# EDUPIC.net
KiCad netlist of a schematic drawn in EAGLE
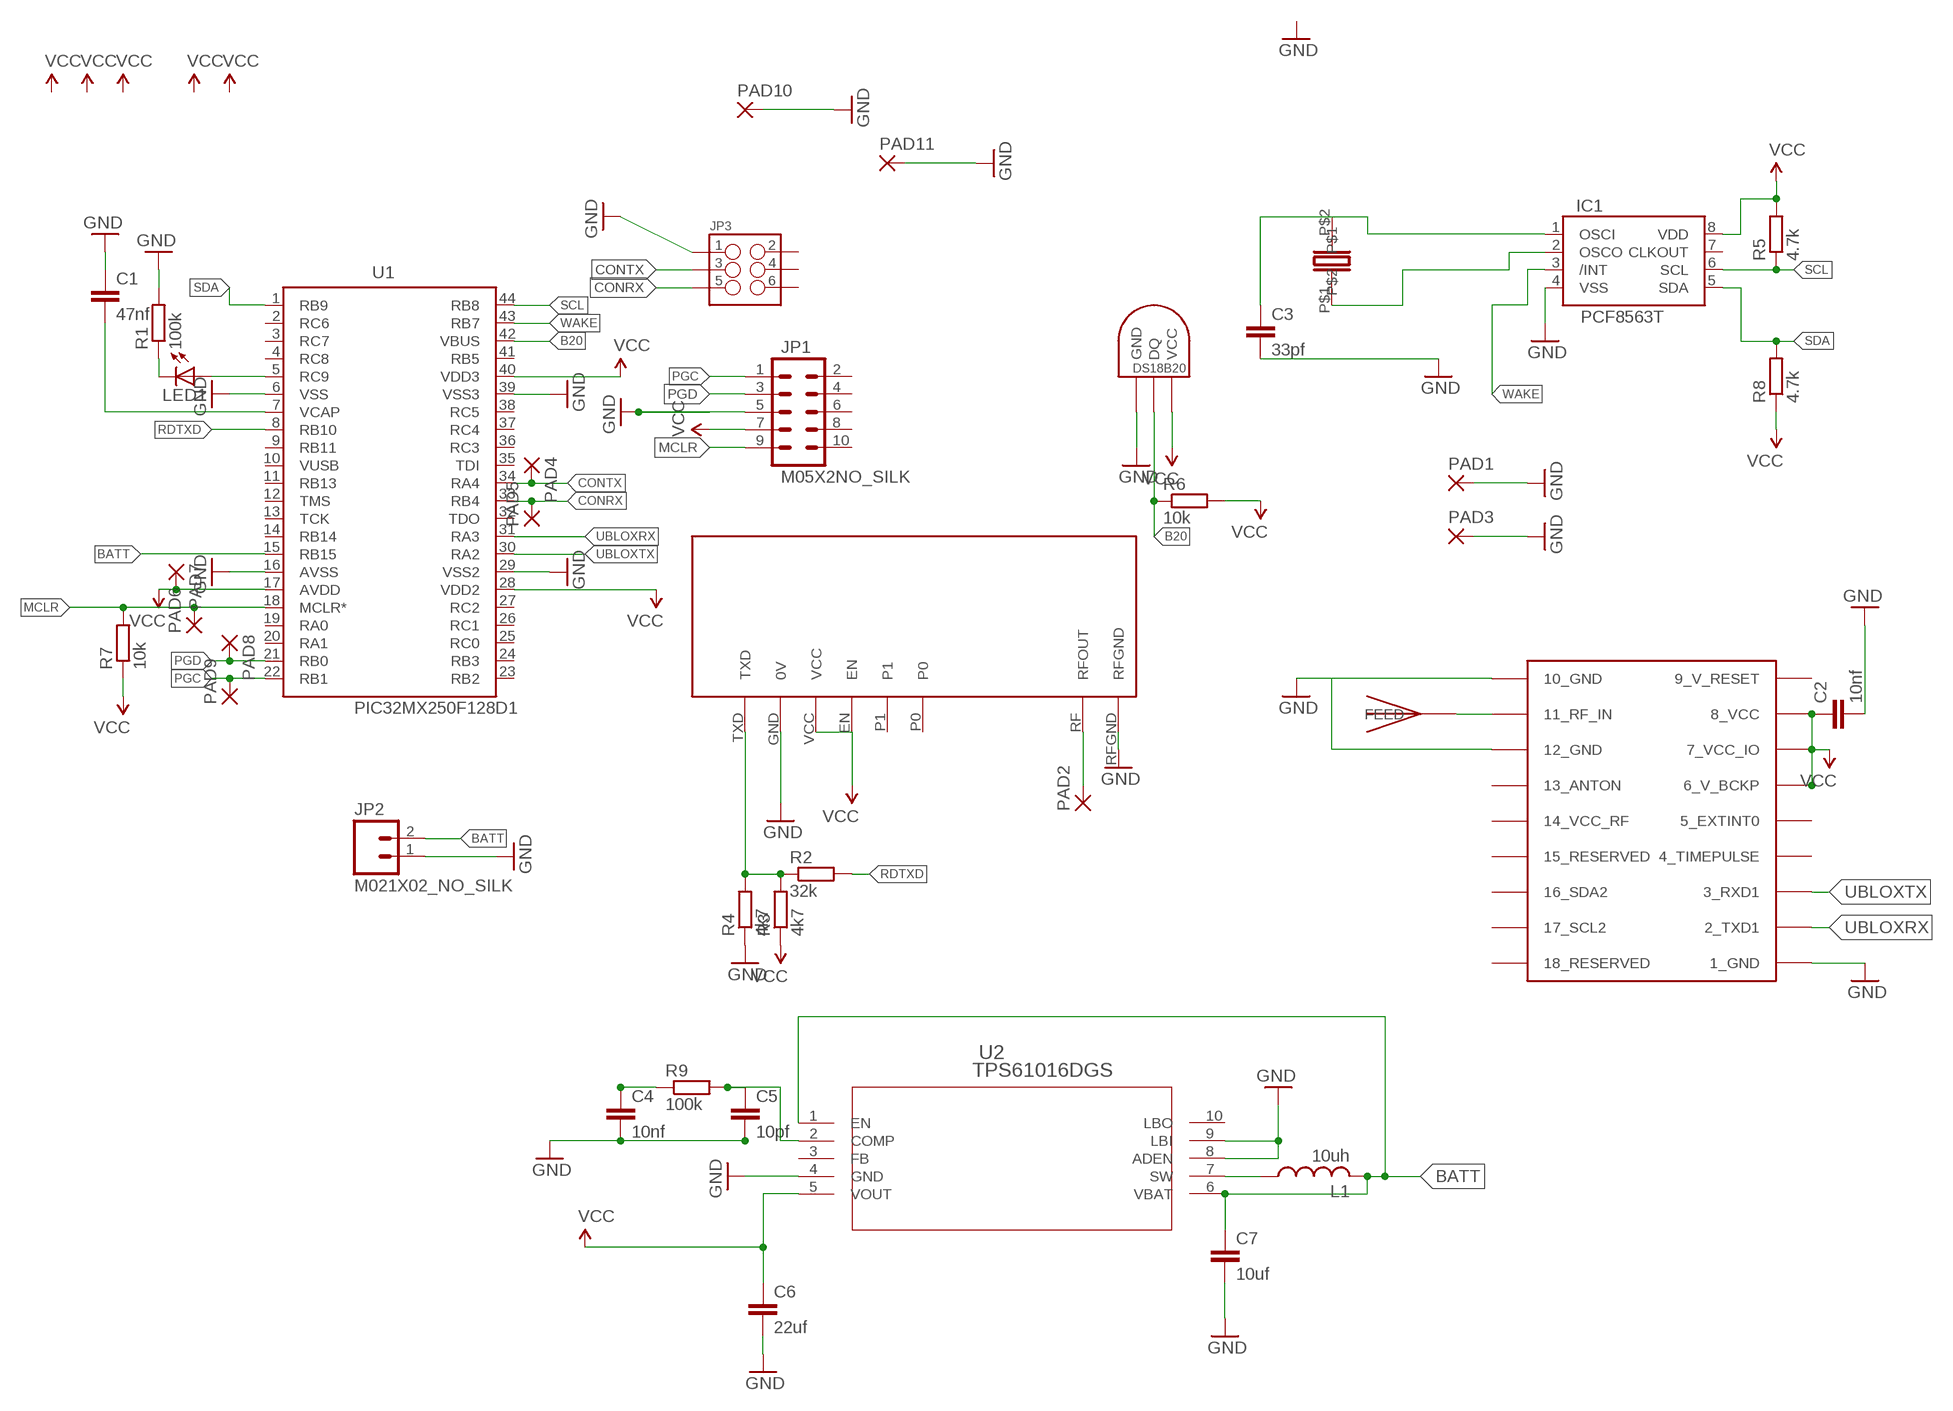
[diagram p0: schematic, sheet 1]

(export (version "E")
  (design (tool "Eeschema 10.0.6"))
  (components
    (comp (ref "C1")
      (value "47nf")
      (footprint "eagle-import:C1206")
      (libsource (lib "eagle-import") (part "C-EUC1206"))
    )
    (comp (ref "C2")
      (value "10nf")
      (footprint "eagle-import:C1206")
      (libsource (lib "eagle-import") (part "C-EUC1206"))
    )
    (comp (ref "C3")
      (value "33pf")
      (footprint "eagle-import:C0805")
      (libsource (lib "eagle-import") (part "C-EUC0805"))
    )
    (comp (ref "C4")
      (value "10nf")
      (footprint "eagle-import:C0805")
      (libsource (lib "eagle-import") (part "C-EUC0805"))
    )
    (comp (ref "C5")
      (value "10pf")
      (footprint "eagle-import:C0805")
      (libsource (lib "eagle-import") (part "C-EUC0805"))
    )
    (comp (ref "C6")
      (value "22uf")
      (footprint "eagle-import:C1812")
      (libsource (lib "eagle-import") (part "C-EUC1812"))
    )
    (comp (ref "C7")
      (value "10uf")
      (footprint "eagle-import:C1206")
      (libsource (lib "eagle-import") (part "C-EUC1206"))
    )
    (comp (ref "IC1")
      (value "PCF8563T")
      (footprint "eagle-import:SO8")
      (libsource (lib "eagle-import") (part "PCF8563T"))
    )
    (comp (ref "JP1")
      (value "M05X2NO_SILK")
      (footprint "eagle-import:2X5_NOSILK")
      (libsource (lib "eagle-import") (part "M05X2NO_SILK"))
    )
    (comp (ref "JP2")
      (value "M021X02_NO_SILK")
      (footprint "eagle-import:1X02_NO_SILK")
      (libsource (lib "eagle-import") (part "M021X02_NO_SILK"))
    )
    (comp (ref "JP3")
      (value "M03X2NO_SILK")
      (footprint "eagle-import:2X3-NS")
      (libsource (lib "eagle-import") (part "M03X2NO_SILK"))
    )
    (comp (ref "L1")
      (value "10uh")
      (footprint "eagle-import:PIS2816")
      (libsource (lib "eagle-import") (part "L-USPIS2816"))
    )
    (comp (ref "LED1")
      (value "LEDCHIP-LED0805")
      (footprint "eagle-import:CHIP-LED0805")
      (libsource (lib "eagle-import") (part "LEDCHIP-LED0805"))
    )
    (comp (ref "PAD1")
      (value "SMD5")
      (footprint "eagle-import:SMD2,54-5,08")
      (libsource (lib "eagle-import") (part "SMD5"))
    )
    (comp (ref "PAD2")
      (value "SMD5")
      (footprint "eagle-import:SMD2,54-5,08")
      (libsource (lib "eagle-import") (part "SMD5"))
    )
    (comp (ref "PAD3")
      (value "SMD5")
      (footprint "eagle-import:SMD2,54-5,08")
      (libsource (lib "eagle-import") (part "SMD5"))
    )
    (comp (ref "PAD4")
      (value "SMD2")
      (footprint "eagle-import:SMD1,27-2,54")
      (libsource (lib "eagle-import") (part "SMD2"))
    )
    (comp (ref "PAD5")
      (value "SMD2")
      (footprint "eagle-import:SMD1,27-2,54")
      (libsource (lib "eagle-import") (part "SMD2"))
    )
    (comp (ref "PAD6")
      (value "SMD2")
      (footprint "eagle-import:SMD1,27-2,54")
      (libsource (lib "eagle-import") (part "SMD2"))
    )
    (comp (ref "PAD7")
      (value "SMD2")
      (footprint "eagle-import:SMD1,27-2,54")
      (libsource (lib "eagle-import") (part "SMD2"))
    )
    (comp (ref "PAD8")
      (value "SMD2")
      (footprint "eagle-import:SMD1,27-2,54")
      (libsource (lib "eagle-import") (part "SMD2"))
    )
    (comp (ref "PAD9")
      (value "SMD2")
      (footprint "eagle-import:SMD1,27-2,54")
      (libsource (lib "eagle-import") (part "SMD2"))
    )
    (comp (ref "PAD10")
      (value "SMD2")
      (footprint "eagle-import:SMD1,27-2,54")
      (libsource (lib "eagle-import") (part "SMD2"))
    )
    (comp (ref "PAD11")
      (value "SMD2")
      (footprint "eagle-import:SMD1,27-2,54")
      (libsource (lib "eagle-import") (part "SMD2"))
    )
    (comp (ref "R1")
      (value "100k")
      (footprint "eagle-import:R0603")
      (libsource (lib "eagle-import") (part "R-EU_R0603"))
    )
    (comp (ref "R2")
      (value "32k")
      (footprint "eagle-import:R1206")
      (libsource (lib "eagle-import") (part "R-EU_R1206"))
    )
    (comp (ref "R3")
      (value "4k7")
      (footprint "eagle-import:R0805")
      (libsource (lib "eagle-import") (part "R-EU_R0805"))
    )
    (comp (ref "R4")
      (value "4k7")
      (footprint "eagle-import:R0805")
      (libsource (lib "eagle-import") (part "R-EU_R0805"))
    )
    (comp (ref "R5")
      (value "4.7k")
      (footprint "eagle-import:R0603")
      (libsource (lib "eagle-import") (part "R-EU_R0603"))
    )
    (comp (ref "R6")
      (value "10k")
      (footprint "eagle-import:R0603")
      (libsource (lib "eagle-import") (part "R-EU_R0603"))
    )
    (comp (ref "R7")
      (value "10k")
      (footprint "eagle-import:R0603")
      (libsource (lib "eagle-import") (part "R-EU_R0603"))
    )
    (comp (ref "R8")
      (value "4.7k")
      (footprint "eagle-import:R0603")
      (libsource (lib "eagle-import") (part "R-EU_R0603"))
    )
    (comp (ref "R9")
      (value "100k")
      (footprint "eagle-import:R0805")
      (libsource (lib "eagle-import") (part "R-EU_R0805"))
    )
    (comp (ref "U$1")
      (value "RADIOMETRIX-MTX2")
      (footprint "eagle-import:RADIOMETRIX-MTX2")
      (libsource (lib "eagle-import") (part "RADIOMETRIX-MTX2"))
    )
    (comp (ref "U$2")
      (value "DS1820SOIC")
      (footprint "eagle-import:DS18B20_SOIC")
      (libsource (lib "eagle-import") (part "DS1820SOIC"))
    )
    (comp (ref "U$3")
      (value "UBLOX_MAX")
      (footprint "eagle-import:UBLOX_MAX")
      (libsource (lib "eagle-import") (part "UBLOX_MAX"))
    )
    (comp (ref "U$4")
      (value "JTI_ANTENNA-1575AT43A40")
      (footprint "eagle-import:JTI_ANTENNA-1575AT43A40")
      (libsource (lib "eagle-import") (part "JTI_ANTENNA-1575AT43A40"))
    )
    (comp (ref "U1")
      (value "PIC32MX250F128D1")
      (footprint "eagle-import:QFP80P1200X1200X120-44N")
      (libsource (lib "eagle-import") (part "PIC32MX250F128D1"))
    )
    (comp (ref "U2")
      (value "TPS61016DGS")
      (footprint "eagle-import:DGS10")
      (fields (field (name "RSPARTNUMBER") "5171220"))
      (libsource (lib "eagle-import") (part "TPS61016DGS"))
    )
    (comp (ref "XTAL")
      (value "3.2X1.5")
      (footprint "eagle-import:3.2X1.5")
      (libsource (lib "eagle-import") (part "3.2X1.5"))
    )
  )
  (nets
    (net (code "1") (name "/9_V_RESET") (class "Default")
      (node (ref "U$3") (pin "9_V_RESET") (pinfunction "9_V_RESET_9_V_RESET") (pintype "power_in"))
    )
    (net (code "2") (name "B20") (class "Default")
      (node (ref "R6") (pin "1") (pinfunction "1_1") (pintype "passive"))
      (node (ref "U$2") (pin "DQ") (pinfunction "DQ_DQ") (pintype "bidirectional"))
      (node (ref "U1") (pin "42") (pinfunction "VBUS_42") (pintype "passive"))
    )
    (net (code "3") (name "BATT") (class "Default")
      (node (ref "C7") (pin "1") (pinfunction "1_1") (pintype "passive"))
      (node (ref "JP2") (pin "2") (pinfunction "2_2") (pintype "passive"))
      (node (ref "L1") (pin "2") (pinfunction "2_2") (pintype "passive"))
      (node (ref "U1") (pin "15") (pinfunction "RB15_15") (pintype "bidirectional"))
      (node (ref "U2") (pin "1") (pinfunction "EN_1") (pintype "input"))
      (node (ref "U2") (pin "6") (pinfunction "VBAT_6") (pintype "power_in"))
    )
    (net (code "4") (name "CONRX") (class "Default")
      (node (ref "JP3") (pin "5") (pinfunction "5_5") (pintype "bidirectional"))
      (node (ref "PAD5") (pin "1") (pinfunction "P_1") (pintype "passive"))
      (node (ref "U1") (pin "33") (pinfunction "RB4_33") (pintype "bidirectional"))
    )
    (net (code "5") (name "CONTX") (class "Default")
      (node (ref "JP3") (pin "3") (pinfunction "3_3") (pintype "bidirectional"))
      (node (ref "PAD4") (pin "1") (pinfunction "P_1") (pintype "passive"))
      (node (ref "U1") (pin "34") (pinfunction "RA4_34") (pintype "bidirectional"))
    )
    (net (code "6") (name "GND") (class "Default")
      (node (ref "C1") (pin "1") (pinfunction "1_1") (pintype "passive"))
      (node (ref "C2") (pin "2") (pinfunction "2_2") (pintype "passive"))
      (node (ref "C3") (pin "2") (pinfunction "2_2") (pintype "passive"))
      (node (ref "C4") (pin "2") (pinfunction "2_2") (pintype "passive"))
      (node (ref "C5") (pin "2") (pinfunction "2_2") (pintype "passive"))
      (node (ref "C6") (pin "2") (pinfunction "2_2") (pintype "passive"))
      (node (ref "C7") (pin "2") (pinfunction "2_2") (pintype "passive"))
      (node (ref "IC1") (pin "4") (pinfunction "VSS_4") (pintype "bidirectional"))
      (node (ref "JP1") (pin "5") (pinfunction "5_5") (pintype "passive"))
      (node (ref "JP2") (pin "1") (pinfunction "1_1") (pintype "passive"))
      (node (ref "JP3") (pin "1") (pinfunction "1_1") (pintype "bidirectional"))
      (node (ref "PAD1") (pin "1") (pinfunction "P_1") (pintype "passive"))
      (node (ref "PAD10") (pin "1") (pinfunction "P_1") (pintype "passive"))
      (node (ref "PAD11") (pin "1") (pinfunction "P_1") (pintype "passive"))
      (node (ref "PAD3") (pin "1") (pinfunction "P_1") (pintype "passive"))
      (node (ref "R1") (pin "2") (pinfunction "2_2") (pintype "passive"))
      (node (ref "R4") (pin "1") (pinfunction "1_1") (pintype "passive"))
      (node (ref "U$1") (pin "GND") (pinfunction "0V_GND") (pintype "bidirectional"))
      (node (ref "U$1") (pin "RFGND") (pinfunction "RFGND_RFGND") (pintype "bidirectional"))
      (node (ref "U$2") (pin "GND") (pinfunction "GND_GND") (pintype "power_in"))
      (node (ref "U$3") (pin "10_GND") (pinfunction "10_GND_10_GND") (pintype "power_in"))
      (node (ref "U$3") (pin "12_GND") (pinfunction "12_GND_12_GND") (pintype "power_in"))
      (node (ref "U$3") (pin "1_GND") (pinfunction "1_GND_1_GND") (pintype "power_in"))
      (node (ref "U1") (pin "16") (pinfunction "AVSS_16") (pintype "power_in"))
      (node (ref "U1") (pin "29") (pinfunction "VSS2_29") (pintype "power_in"))
      (node (ref "U1") (pin "39") (pinfunction "VSS3_39") (pintype "power_in"))
      (node (ref "U1") (pin "6") (pinfunction "VSS_6") (pintype "power_in"))
      (node (ref "U2") (pin "4") (pinfunction "GND_4") (pintype "power_in"))
      (node (ref "U2") (pin "8") (pinfunction "ADEN_8") (pintype "input"))
      (node (ref "U2") (pin "9") (pinfunction "LBI_9") (pintype "input"))
    )
    (net (code "7") (name "MCLR") (class "Default")
      (node (ref "JP1") (pin "9") (pinfunction "9_9") (pintype "passive"))
      (node (ref "PAD6") (pin "1") (pinfunction "P_1") (pintype "passive"))
      (node (ref "R7") (pin "2") (pinfunction "2_2") (pintype "passive"))
      (node (ref "U1") (pin "18") (pinfunction "MCLR*_18") (pintype "input"))
    )
    (net (code "8") (name "Net-(C4-Pad1)") (class "Default")
      (node (ref "C4") (pin "1") (pinfunction "1_1") (pintype "passive"))
      (node (ref "R9") (pin "1") (pinfunction "1_1") (pintype "passive"))
    )
    (net (code "9") (name "Net-(IC1-OSCI)") (class "Default")
      (node (ref "C3") (pin "1") (pinfunction "1_1") (pintype "passive"))
      (node (ref "IC1") (pin "1") (pinfunction "OSCI_1") (pintype "bidirectional"))
      (node (ref "XTAL") (pin "P$2") (pinfunction "P$2_P$2") (pintype "bidirectional"))
    )
    (net (code "10") (name "Net-(IC1-OSCO)") (class "Default")
      (node (ref "IC1") (pin "2") (pinfunction "OSCO_2") (pintype "bidirectional"))
      (node (ref "XTAL") (pin "P$1") (pinfunction "P$1_P$1") (pintype "bidirectional"))
    )
    (net (code "11") (name "Net-(LED1-PadC)") (class "Default")
      (node (ref "LED1") (pin "C") (pinfunction "C_C") (pintype "passive"))
      (node (ref "R1") (pin "1") (pinfunction "1_1") (pintype "passive"))
    )
    (net (code "12") (name "Net-(PAD2-P)") (class "Default")
      (node (ref "PAD2") (pin "1") (pinfunction "P_1") (pintype "passive"))
      (node (ref "U$1") (pin "RF") (pinfunction "RFOUT_RF") (pintype "bidirectional"))
    )
    (net (code "13") (name "Net-(R2-Pad1)") (class "Default")
      (node (ref "R2") (pin "1") (pinfunction "1_1") (pintype "passive"))
      (node (ref "R3") (pin "2") (pinfunction "2_2") (pintype "passive"))
      (node (ref "R4") (pin "2") (pinfunction "2_2") (pintype "passive"))
      (node (ref "U$1") (pin "TXD") (pinfunction "TXD_TXD") (pintype "bidirectional"))
    )
    (net (code "14") (name "Net-(U$3-Pad11_RF_IN)") (class "Default")
      (node (ref "U$3") (pin "11_RF_IN") (pinfunction "11_RF_IN_11_RF_IN") (pintype "bidirectional"))
      (node (ref "U$4") (pin "FEED") (pinfunction "FEED_FEED") (pintype "bidirectional"))
    )
    (net (code "15") (name "Net-(U1-RC9)") (class "Default")
      (node (ref "LED1") (pin "A") (pinfunction "A_A") (pintype "passive"))
      (node (ref "U1") (pin "5") (pinfunction "RC9_5") (pintype "bidirectional"))
    )
    (net (code "16") (name "Net-(U1-VCAP)") (class "Default")
      (node (ref "C1") (pin "2") (pinfunction "2_2") (pintype "passive"))
      (node (ref "U1") (pin "7") (pinfunction "VCAP_7") (pintype "bidirectional"))
    )
    (net (code "17") (name "Net-(U2-COMP)") (class "Default")
      (node (ref "C5") (pin "1") (pinfunction "1_1") (pintype "passive"))
      (node (ref "R9") (pin "2") (pinfunction "2_2") (pintype "passive"))
      (node (ref "U2") (pin "2") (pinfunction "COMP_2") (pintype "input"))
    )
    (net (code "18") (name "Net-(U2-SW)") (class "Default")
      (node (ref "L1") (pin "1") (pinfunction "1_1") (pintype "passive"))
      (node (ref "U2") (pin "7") (pinfunction "SW_7") (pintype "input"))
    )
    (net (code "19") (name "PGC") (class "Default")
      (node (ref "JP1") (pin "1") (pinfunction "1_1") (pintype "passive"))
      (node (ref "PAD9") (pin "1") (pinfunction "P_1") (pintype "passive"))
      (node (ref "U1") (pin "22") (pinfunction "RB1_22") (pintype "bidirectional"))
    )
    (net (code "20") (name "PGD") (class "Default")
      (node (ref "JP1") (pin "3") (pinfunction "3_3") (pintype "passive"))
      (node (ref "PAD8") (pin "1") (pinfunction "P_1") (pintype "passive"))
      (node (ref "U1") (pin "21") (pinfunction "RB0_21") (pintype "bidirectional"))
    )
    (net (code "21") (name "RDTXD") (class "Default")
      (node (ref "R2") (pin "2") (pinfunction "2_2") (pintype "passive"))
      (node (ref "U1") (pin "8") (pinfunction "RB10_8") (pintype "bidirectional"))
    )
    (net (code "22") (name "SCL") (class "Default")
      (node (ref "IC1") (pin "6") (pinfunction "SCL_6") (pintype "bidirectional"))
      (node (ref "R5") (pin "1") (pinfunction "1_1") (pintype "passive"))
      (node (ref "U1") (pin "44") (pinfunction "RB8_44") (pintype "bidirectional"))
    )
    (net (code "23") (name "SDA") (class "Default")
      (node (ref "IC1") (pin "5") (pinfunction "SDA_5") (pintype "bidirectional"))
      (node (ref "R8") (pin "2") (pinfunction "2_2") (pintype "passive"))
      (node (ref "U1") (pin "1") (pinfunction "RB9_1") (pintype "bidirectional"))
    )
    (net (code "24") (name "UBLOXRX") (class "Default")
      (node (ref "U$3") (pin "2_TXD1") (pinfunction "2_TXD1_2_TXD1") (pintype "bidirectional"))
      (node (ref "U1") (pin "31") (pinfunction "RA3_31") (pintype "bidirectional"))
    )
    (net (code "25") (name "UBLOXTX") (class "Default")
      (node (ref "U$3") (pin "3_RXD1") (pinfunction "3_RXD1_3_RXD1") (pintype "bidirectional"))
      (node (ref "U1") (pin "30") (pinfunction "RA2_30") (pintype "bidirectional"))
    )
    (net (code "26") (name "VCC") (class "Default")
      (node (ref "C2") (pin "1") (pinfunction "1_1") (pintype "passive"))
      (node (ref "C6") (pin "1") (pinfunction "1_1") (pintype "passive"))
      (node (ref "IC1") (pin "8") (pinfunction "VDD_8") (pintype "bidirectional"))
      (node (ref "JP1") (pin "7") (pinfunction "7_7") (pintype "passive"))
      (node (ref "PAD7") (pin "1") (pinfunction "P_1") (pintype "passive"))
      (node (ref "R3") (pin "1") (pinfunction "1_1") (pintype "passive"))
      (node (ref "R5") (pin "2") (pinfunction "2_2") (pintype "passive"))
      (node (ref "R6") (pin "2") (pinfunction "2_2") (pintype "passive"))
      (node (ref "R7") (pin "1") (pinfunction "1_1") (pintype "passive"))
      (node (ref "R8") (pin "1") (pinfunction "1_1") (pintype "passive"))
      (node (ref "U$1") (pin "EN") (pinfunction "EN_EN") (pintype "bidirectional"))
      (node (ref "U$1") (pin "VCC") (pinfunction "VCC_VCC") (pintype "bidirectional"))
      (node (ref "U$2") (pin "VCC") (pinfunction "VCC_VCC") (pintype "power_in"))
      (node (ref "U$3") (pin "6_V_BCKP") (pinfunction "6_V_BCKP_6_V_BCKP") (pintype "bidirectional"))
      (node (ref "U$3") (pin "7_VCC_IO") (pinfunction "7_VCC_IO_7_VCC_IO") (pintype "power_in"))
      (node (ref "U$3") (pin "8_VCC") (pinfunction "8_VCC_8_VCC") (pintype "power_in"))
      (node (ref "U1") (pin "17") (pinfunction "AVDD_17") (pintype "power_in"))
      (node (ref "U1") (pin "28") (pinfunction "VDD2_28") (pintype "power_in"))
      (node (ref "U1") (pin "40") (pinfunction "VDD3_40") (pintype "power_in"))
      (node (ref "U2") (pin "5") (pinfunction "VOUT_5") (pintype "output"))
    )
    (net (code "27") (name "WAKE") (class "Default")
      (node (ref "IC1") (pin "3") (pinfunction "/INT_3") (pintype "bidirectional"))
      (node (ref "U1") (pin "43") (pinfunction "RB7_43") (pintype "bidirectional"))
    )
    (net (code "28") (name "unconnected-(IC1-CLKOUT-Pad7)") (class "Default")
      (node (ref "IC1") (pin "7") (pinfunction "CLKOUT_7") (pintype "bidirectional"))
    )
    (net (code "29") (name "unconnected-(JP1-Pad2)") (class "Default")
      (node (ref "JP1") (pin "2") (pinfunction "2_2") (pintype "passive"))
    )
    (net (code "30") (name "unconnected-(JP1-Pad4)") (class "Default")
      (node (ref "JP1") (pin "4") (pinfunction "4_4") (pintype "passive"))
    )
    (net (code "31") (name "unconnected-(JP1-Pad6)") (class "Default")
      (node (ref "JP1") (pin "6") (pinfunction "6_6") (pintype "passive"))
    )
    (net (code "32") (name "unconnected-(JP1-Pad8)") (class "Default")
      (node (ref "JP1") (pin "8") (pinfunction "8_8") (pintype "passive"))
    )
    (net (code "33") (name "unconnected-(JP1-Pad10)") (class "Default")
      (node (ref "JP1") (pin "10") (pinfunction "10_10") (pintype "passive"))
    )
    (net (code "34") (name "unconnected-(JP3-Pad2)") (class "Default")
      (node (ref "JP3") (pin "2") (pinfunction "2_2") (pintype "bidirectional"))
    )
    (net (code "35") (name "unconnected-(JP3-Pad4)") (class "Default")
      (node (ref "JP3") (pin "4") (pinfunction "4_4") (pintype "bidirectional"))
    )
    (net (code "36") (name "unconnected-(JP3-Pad6)") (class "Default")
      (node (ref "JP3") (pin "6") (pinfunction "6_6") (pintype "bidirectional"))
    )
    (net (code "37") (name "unconnected-(U$1-PadP0)") (class "Default")
      (node (ref "U$1") (pin "P0") (pinfunction "P0_P0") (pintype "bidirectional"))
    )
    (net (code "38") (name "unconnected-(U$1-PadP1)") (class "Default")
      (node (ref "U$1") (pin "P1") (pinfunction "P1_P1") (pintype "bidirectional"))
    )
    (net (code "39") (name "unconnected-(U$3-Pad4_TIMEPULSE)") (class "Default")
      (node (ref "U$3") (pin "4_TIMEPULSE") (pinfunction "4_TIMEPULSE_4_TIMEPULSE") (pintype "bidirectional"))
    )
    (net (code "40") (name "unconnected-(U$3-Pad5_EXTINT0)") (class "Default")
      (node (ref "U$3") (pin "5_EXTINT0") (pinfunction "5_EXTINT0_5_EXTINT0") (pintype "bidirectional"))
    )
    (net (code "41") (name "unconnected-(U$3-Pad13_ANTON)") (class "Default")
      (node (ref "U$3") (pin "13_ANTON") (pinfunction "13_ANTON_13_ANTON") (pintype "bidirectional"))
    )
    (net (code "42") (name "unconnected-(U$3-Pad14_VCC_RF)") (class "Default")
      (node (ref "U$3") (pin "14_VCC_RF") (pinfunction "14_VCC_RF_14_VCC_RF") (pintype "bidirectional"))
    )
    (net (code "43") (name "unconnected-(U$3-Pad15_RESERVED)") (class "Default")
      (node (ref "U$3") (pin "15_RESERVED") (pinfunction "15_RESERVED_15_RESERVED") (pintype "bidirectional"))
    )
    (net (code "44") (name "unconnected-(U$3-Pad16_SDA2)") (class "Default")
      (node (ref "U$3") (pin "16_SDA2") (pinfunction "16_SDA2_16_SDA2") (pintype "bidirectional"))
    )
    (net (code "45") (name "unconnected-(U$3-Pad17_SCL2)") (class "Default")
      (node (ref "U$3") (pin "17_SCL2") (pinfunction "17_SCL2_17_SCL2") (pintype "bidirectional"))
    )
    (net (code "46") (name "unconnected-(U$3-Pad18_RESERVED)") (class "Default")
      (node (ref "U$3") (pin "18_RESERVED") (pinfunction "18_RESERVED_18_RESERVED") (pintype "bidirectional"))
    )
    (net (code "47") (name "unconnected-(U1-RA0-Pad19)") (class "Default")
      (node (ref "U1") (pin "19") (pinfunction "RA0_19") (pintype "bidirectional"))
    )
    (net (code "48") (name "unconnected-(U1-RA1-Pad20)") (class "Default")
      (node (ref "U1") (pin "20") (pinfunction "RA1_20") (pintype "bidirectional"))
    )
    (net (code "49") (name "unconnected-(U1-RB2-Pad23)") (class "Default")
      (node (ref "U1") (pin "23") (pinfunction "RB2_23") (pintype "bidirectional"))
    )
    (net (code "50") (name "unconnected-(U1-RB3-Pad24)") (class "Default")
      (node (ref "U1") (pin "24") (pinfunction "RB3_24") (pintype "bidirectional"))
    )
    (net (code "51") (name "unconnected-(U1-RB5-Pad41)") (class "Default")
      (node (ref "U1") (pin "41") (pinfunction "RB5_41") (pintype "bidirectional"))
    )
    (net (code "52") (name "unconnected-(U1-RB11-Pad9)") (class "Default")
      (node (ref "U1") (pin "9") (pinfunction "RB11_9") (pintype "bidirectional"))
    )
    (net (code "53") (name "unconnected-(U1-RB13-Pad11)") (class "Default")
      (node (ref "U1") (pin "11") (pinfunction "RB13_11") (pintype "bidirectional"))
    )
    (net (code "54") (name "unconnected-(U1-RB14-Pad14)") (class "Default")
      (node (ref "U1") (pin "14") (pinfunction "RB14_14") (pintype "bidirectional"))
    )
    (net (code "55") (name "unconnected-(U1-RC0-Pad25)") (class "Default")
      (node (ref "U1") (pin "25") (pinfunction "RC0_25") (pintype "bidirectional"))
    )
    (net (code "56") (name "unconnected-(U1-RC1-Pad26)") (class "Default")
      (node (ref "U1") (pin "26") (pinfunction "RC1_26") (pintype "bidirectional"))
    )
    (net (code "57") (name "unconnected-(U1-RC2-Pad27)") (class "Default")
      (node (ref "U1") (pin "27") (pinfunction "RC2_27") (pintype "bidirectional"))
    )
    (net (code "58") (name "unconnected-(U1-RC3-Pad36)") (class "Default")
      (node (ref "U1") (pin "36") (pinfunction "RC3_36") (pintype "bidirectional"))
    )
    (net (code "59") (name "unconnected-(U1-RC4-Pad37)") (class "Default")
      (node (ref "U1") (pin "37") (pinfunction "RC4_37") (pintype "bidirectional"))
    )
    (net (code "60") (name "unconnected-(U1-RC5-Pad38)") (class "Default")
      (node (ref "U1") (pin "38") (pinfunction "RC5_38") (pintype "bidirectional"))
    )
    (net (code "61") (name "unconnected-(U1-RC6-Pad2)") (class "Default")
      (node (ref "U1") (pin "2") (pinfunction "RC6_2") (pintype "bidirectional"))
    )
    (net (code "62") (name "unconnected-(U1-RC7-Pad3)") (class "Default")
      (node (ref "U1") (pin "3") (pinfunction "RC7_3") (pintype "bidirectional"))
    )
    (net (code "63") (name "unconnected-(U1-RC8-Pad4)") (class "Default")
      (node (ref "U1") (pin "4") (pinfunction "RC8_4") (pintype "bidirectional"))
    )
    (net (code "64") (name "unconnected-(U1-TCK-Pad13)") (class "Default")
      (node (ref "U1") (pin "13") (pinfunction "TCK_13") (pintype "input"))
    )
    (net (code "65") (name "unconnected-(U1-TDI-Pad35)") (class "Default")
      (node (ref "U1") (pin "35") (pinfunction "TDI_35") (pintype "input"))
    )
    (net (code "66") (name "unconnected-(U1-TDO-Pad32)") (class "Default")
      (node (ref "U1") (pin "32") (pinfunction "TDO_32") (pintype "output"))
    )
    (net (code "67") (name "unconnected-(U1-TMS-Pad12)") (class "Default")
      (node (ref "U1") (pin "12") (pinfunction "TMS_12") (pintype "input"))
    )
    (net (code "68") (name "unconnected-(U1-VUSB-Pad10)") (class "Default")
      (node (ref "U1") (pin "10") (pinfunction "VUSB_10") (pintype "passive"))
    )
    (net (code "69") (name "unconnected-(U2-FB-Pad3)") (class "Default")
      (node (ref "U2") (pin "3") (pinfunction "FB_3") (pintype "input"))
    )
    (net (code "70") (name "unconnected-(U2-LBO-Pad10)") (class "Default")
      (node (ref "U2") (pin "10") (pinfunction "LBO_10") (pintype "output"))
    )
  )
)
